# microzed_schematic.net
KiCad netlist of a schematic drawn in Altium Designer
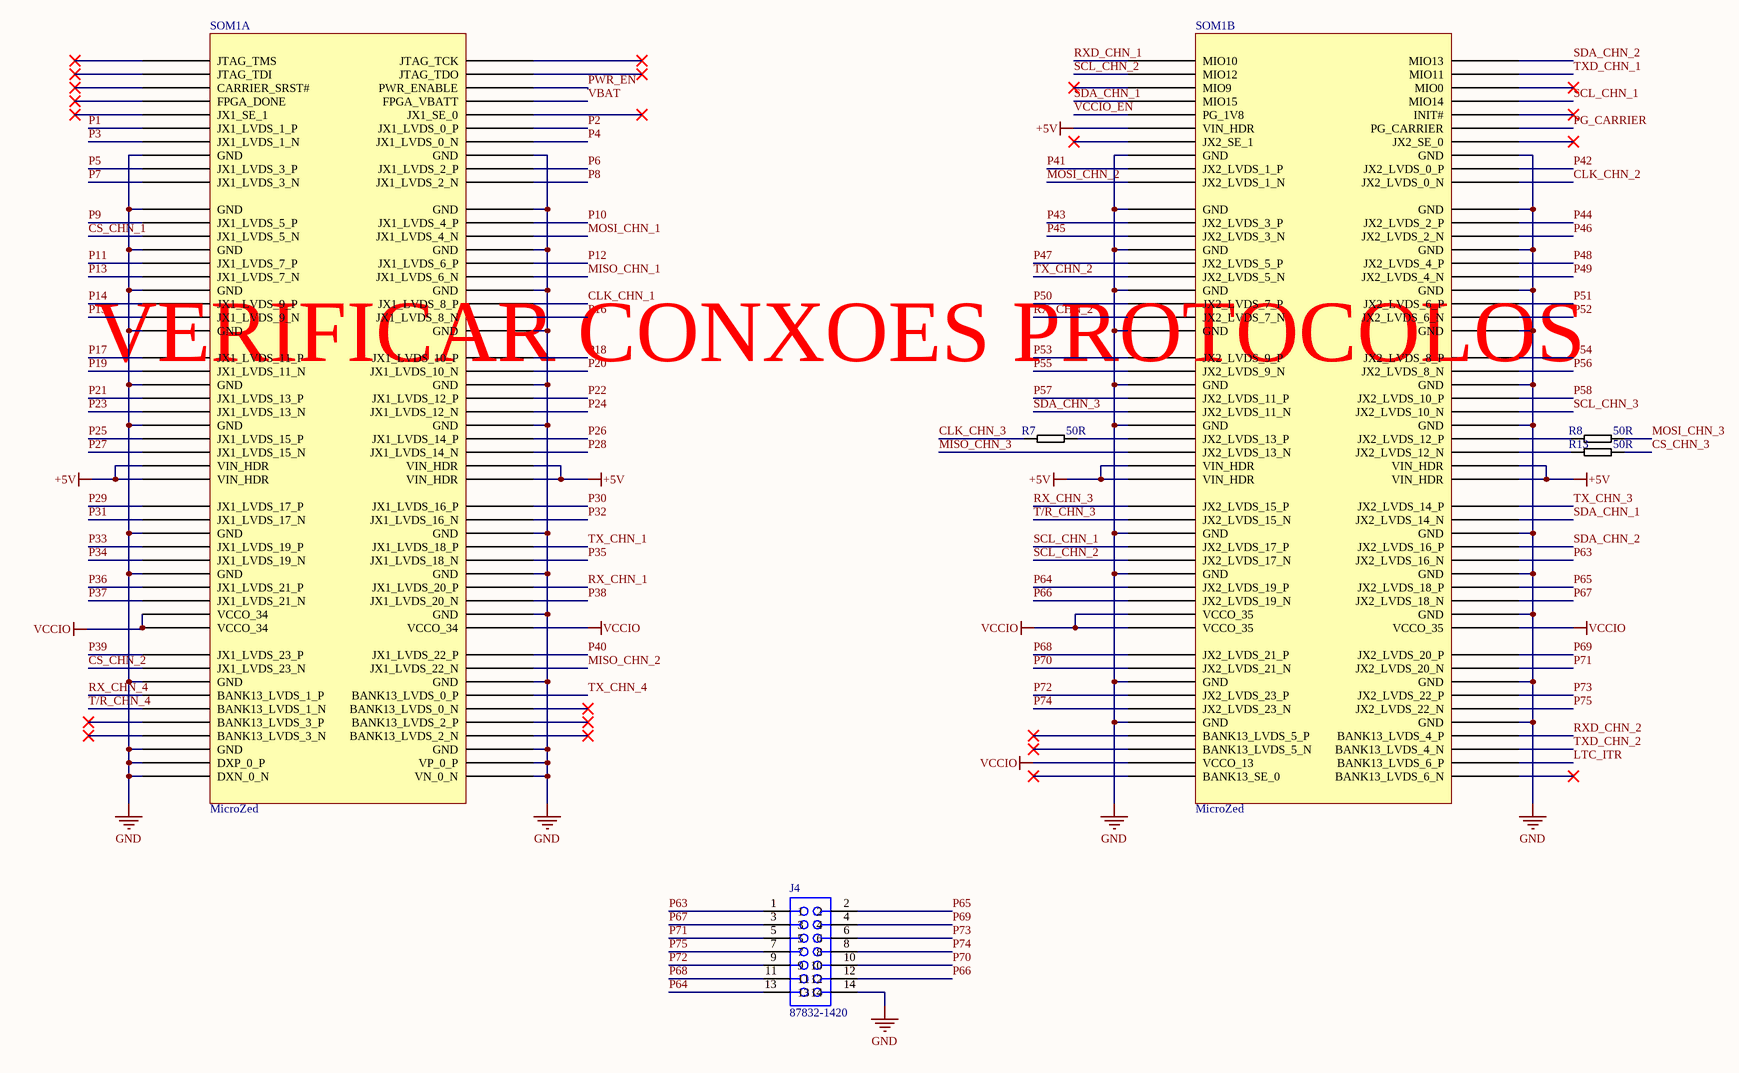
[diagram p0: microzed_schematic.SchDoc]

(export (version "E")
  (design (tool "Eeschema 10.0.6"))
  (components
    (comp (ref "J4")
      (value "87832-1420")
      (footprint "SAMTEC_TSW-107-05-F-D")
      (description "Connector Header Surface Mount 14 position 0.079 _2.00mm_")
      (fields (field (name "MF") "Molex") (field (name "MANUFACTURER PART NUMBER") "TSW-107-05-F-D"))
      (libsource (lib "flatsat_platform_2") (part "87832-1420"))
    )
    (comp (ref "R7")
      (value "50R")
      (footprint "R0603_HD")
      (description "RES SMD 50 OHM 1% 1/10W 0603")
      (fields (field (name "MANUFACTURER") "Vishay Dale") (field (name "TOLERANCE") "1%"))
      (libsource (lib "Resistor") (part "CRCW060350R0FKEA"))
    )
    (comp (ref "R8")
      (value "50R")
      (footprint "R0603_HD")
      (description "RES SMD 50 OHM 1% 1/10W 0603")
      (fields (field (name "MANUFACTURER") "Vishay Dale") (field (name "TOLERANCE") "1%"))
      (libsource (lib "Resistor") (part "CRCW060350R0FKEA"))
    )
    (comp (ref "R13")
      (value "50R")
      (footprint "R0603_HD")
      (description "RES SMD 50 OHM 1% 1/10W 0603")
      (fields (field (name "MANUFACTURER") "Vishay Dale") (field (name "TOLERANCE") "1%"))
      (libsource (lib "Resistor") (part "CRCW060350R0FKEA"))
    )
    (comp (ref "SOM1")
      (value "MicroZed")
      (footprint "MicroZedSOM")
      (description "MicroZed SOM Carrier Footprint")
      (fields (field (name "MANUFACTURER PART NUMBER") "61083-101400LF"))
      (libsource (lib "flatsat_platform_2") (part "MicroZed_SOM"))
    )
  )
  (nets
    (net (code "1") (name "+5V") (class "Default")
      (node (ref "SOM1") (pin "JX1-57") (pinfunction "VIN_HDR_JX1-57") (pintype "passive"))
      (node (ref "SOM1") (pin "JX1-58") (pinfunction "VIN_HDR_JX1-58") (pintype "passive"))
      (node (ref "SOM1") (pin "JX1-59") (pinfunction "VIN_HDR_JX1-59") (pintype "passive"))
      (node (ref "SOM1") (pin "JX1-60") (pinfunction "VIN_HDR_JX1-60") (pintype "passive"))
      (node (ref "SOM1") (pin "JX2-12") (pinfunction "VIN_HDR_JX2-12") (pintype "passive"))
      (node (ref "SOM1") (pin "JX2-57") (pinfunction "VIN_HDR_JX2-57") (pintype "passive"))
      (node (ref "SOM1") (pin "JX2-58") (pinfunction "VIN_HDR_JX2-58") (pintype "passive"))
      (node (ref "SOM1") (pin "JX2-59") (pinfunction "VIN_HDR_JX2-59") (pintype "passive"))
      (node (ref "SOM1") (pin "JX2-60") (pinfunction "VIN_HDR_JX2-60") (pintype "passive"))
    )
    (net (code "2") (name "/CLK_CHN_1") (class "Default")
      (node (ref "SOM1") (pin "JX1-35") (pinfunction "JX1_LVDS_8_P_JX1-35") (pintype "passive"))
    )
    (net (code "3") (name "/CLK_CHN_2") (class "Default")
      (node (ref "SOM1") (pin "JX2-19") (pinfunction "JX2_LVDS_0_N_JX2-19") (pintype "passive"))
    )
    (net (code "4") (name "/CLK_CHN_3") (class "Default")
      (node (ref "R7") (pin "1") (pinfunction "1_1") (pintype "passive"))
    )
    (net (code "5") (name "/CS_CHN_1") (class "Default")
      (node (ref "SOM1") (pin "JX1-26") (pinfunction "JX1_LVDS_5_N_JX1-26") (pintype "passive"))
    )
    (net (code "6") (name "/CS_CHN_2") (class "Default")
      (node (ref "SOM1") (pin "JX1-84") (pinfunction "JX1_LVDS_23_N_JX1-84") (pintype "passive"))
    )
    (net (code "7") (name "/CS_CHN_3") (class "Default")
      (node (ref "R13") (pin "2") (pinfunction "2_2") (pintype "passive"))
    )
    (net (code "8") (name "/LTC_ITR") (class "Default")
      (node (ref "SOM1") (pin "JX2-97") (pinfunction "BANK13_LVDS_6_P_JX2-97") (pintype "passive"))
    )
    (net (code "9") (name "/MISO_CHN_1") (class "Default")
      (node (ref "SOM1") (pin "JX1-31") (pinfunction "JX1_LVDS_6_N_JX1-31") (pintype "passive"))
    )
    (net (code "10") (name "/MISO_CHN_2") (class "Default")
      (node (ref "SOM1") (pin "JX1-83") (pinfunction "JX1_LVDS_22_N_JX1-83") (pintype "passive"))
    )
    (net (code "11") (name "/MISO_CHN_3") (class "Default")
      (node (ref "SOM1") (pin "JX2-56") (pinfunction "JX2_LVDS_13_N_JX2-56") (pintype "passive"))
    )
    (net (code "12") (name "/MOSI_CHN_1") (class "Default")
      (node (ref "SOM1") (pin "JX1-25") (pinfunction "JX1_LVDS_4_N_JX1-25") (pintype "passive"))
    )
    (net (code "13") (name "/MOSI_CHN_2") (class "Default")
      (node (ref "SOM1") (pin "JX2-20") (pinfunction "JX2_LVDS_1_N_JX2-20") (pintype "passive"))
    )
    (net (code "14") (name "/MOSI_CHN_3") (class "Default")
      (node (ref "R8") (pin "2") (pinfunction "2_2") (pintype "passive"))
    )
    (net (code "15") (name "/P1") (class "Default")
      (node (ref "SOM1") (pin "JX1-12") (pinfunction "JX1_LVDS_1_P_JX1-12") (pintype "passive"))
    )
    (net (code "16") (name "/P2") (class "Default")
      (node (ref "SOM1") (pin "JX1-11") (pinfunction "JX1_LVDS_0_P_JX1-11") (pintype "passive"))
    )
    (net (code "17") (name "/P3") (class "Default")
      (node (ref "SOM1") (pin "JX1-14") (pinfunction "JX1_LVDS_1_N_JX1-14") (pintype "passive"))
    )
    (net (code "18") (name "/P4") (class "Default")
      (node (ref "SOM1") (pin "JX1-13") (pinfunction "JX1_LVDS_0_N_JX1-13") (pintype "passive"))
    )
    (net (code "19") (name "/P5") (class "Default")
      (node (ref "SOM1") (pin "JX1-18") (pinfunction "JX1_LVDS_3_P_JX1-18") (pintype "passive"))
    )
    (net (code "20") (name "/P6") (class "Default")
      (node (ref "SOM1") (pin "JX1-17") (pinfunction "JX1_LVDS_2_P_JX1-17") (pintype "passive"))
    )
    (net (code "21") (name "/P7") (class "Default")
      (node (ref "SOM1") (pin "JX1-20") (pinfunction "JX1_LVDS_3_N_JX1-20") (pintype "passive"))
    )
    (net (code "22") (name "/P8") (class "Default")
      (node (ref "SOM1") (pin "JX1-19") (pinfunction "JX1_LVDS_2_N_JX1-19") (pintype "passive"))
    )
    (net (code "23") (name "/P9") (class "Default")
      (node (ref "SOM1") (pin "JX1-24") (pinfunction "JX1_LVDS_5_P_JX1-24") (pintype "passive"))
    )
    (net (code "24") (name "/P10") (class "Default")
      (node (ref "SOM1") (pin "JX1-23") (pinfunction "JX1_LVDS_4_P_JX1-23") (pintype "passive"))
    )
    (net (code "25") (name "/P11") (class "Default")
      (node (ref "SOM1") (pin "JX1-30") (pinfunction "JX1_LVDS_7_P_JX1-30") (pintype "passive"))
    )
    (net (code "26") (name "/P12") (class "Default")
      (node (ref "SOM1") (pin "JX1-29") (pinfunction "JX1_LVDS_6_P_JX1-29") (pintype "passive"))
    )
    (net (code "27") (name "/P13") (class "Default")
      (node (ref "SOM1") (pin "JX1-32") (pinfunction "JX1_LVDS_7_N_JX1-32") (pintype "passive"))
    )
    (net (code "28") (name "/P14") (class "Default")
      (node (ref "SOM1") (pin "JX1-36") (pinfunction "JX1_LVDS_9_P_JX1-36") (pintype "passive"))
    )
    (net (code "29") (name "/P15") (class "Default")
      (node (ref "SOM1") (pin "JX1-38") (pinfunction "JX1_LVDS_9_N_JX1-38") (pintype "passive"))
    )
    (net (code "30") (name "/P16") (class "Default")
      (node (ref "SOM1") (pin "JX1-37") (pinfunction "JX1_LVDS_8_N_JX1-37") (pintype "passive"))
    )
    (net (code "31") (name "/P17") (class "Default")
      (node (ref "SOM1") (pin "JX1-42") (pinfunction "JX1_LVDS_11_P_JX1-42") (pintype "passive"))
    )
    (net (code "32") (name "/P18") (class "Default")
      (node (ref "SOM1") (pin "JX1-41") (pinfunction "JX1_LVDS_10_P_JX1-41") (pintype "passive"))
    )
    (net (code "33") (name "/P19") (class "Default")
      (node (ref "SOM1") (pin "JX1-44") (pinfunction "JX1_LVDS_11_N_JX1-44") (pintype "passive"))
    )
    (net (code "34") (name "/P20") (class "Default")
      (node (ref "SOM1") (pin "JX1-43") (pinfunction "JX1_LVDS_10_N_JX1-43") (pintype "passive"))
    )
    (net (code "35") (name "/P21") (class "Default")
      (node (ref "SOM1") (pin "JX1-48") (pinfunction "JX1_LVDS_13_P_JX1-48") (pintype "passive"))
    )
    (net (code "36") (name "/P22") (class "Default")
      (node (ref "SOM1") (pin "JX1-47") (pinfunction "JX1_LVDS_12_P_JX1-47") (pintype "passive"))
    )
    (net (code "37") (name "/P23") (class "Default")
      (node (ref "SOM1") (pin "JX1-50") (pinfunction "JX1_LVDS_13_N_JX1-50") (pintype "passive"))
    )
    (net (code "38") (name "/P24") (class "Default")
      (node (ref "SOM1") (pin "JX1-49") (pinfunction "JX1_LVDS_12_N_JX1-49") (pintype "passive"))
    )
    (net (code "39") (name "/P25") (class "Default")
      (node (ref "SOM1") (pin "JX1-54") (pinfunction "JX1_LVDS_15_P_JX1-54") (pintype "passive"))
    )
    (net (code "40") (name "/P26") (class "Default")
      (node (ref "SOM1") (pin "JX1-53") (pinfunction "JX1_LVDS_14_P_JX1-53") (pintype "passive"))
    )
    (net (code "41") (name "/P27") (class "Default")
      (node (ref "SOM1") (pin "JX1-56") (pinfunction "JX1_LVDS_15_N_JX1-56") (pintype "passive"))
    )
    (net (code "42") (name "/P28") (class "Default")
      (node (ref "SOM1") (pin "JX1-55") (pinfunction "JX1_LVDS_14_N_JX1-55") (pintype "passive"))
    )
    (net (code "43") (name "/P29") (class "Default")
      (node (ref "SOM1") (pin "JX1-62") (pinfunction "JX1_LVDS_17_P_JX1-62") (pintype "passive"))
    )
    (net (code "44") (name "/P30") (class "Default")
      (node (ref "SOM1") (pin "JX1-61") (pinfunction "JX1_LVDS_16_P_JX1-61") (pintype "passive"))
    )
    (net (code "45") (name "/P31") (class "Default")
      (node (ref "SOM1") (pin "JX1-64") (pinfunction "JX1_LVDS_17_N_JX1-64") (pintype "passive"))
    )
    (net (code "46") (name "/P32") (class "Default")
      (node (ref "SOM1") (pin "JX1-63") (pinfunction "JX1_LVDS_16_N_JX1-63") (pintype "passive"))
    )
    (net (code "47") (name "/P33") (class "Default")
      (node (ref "SOM1") (pin "JX1-68") (pinfunction "JX1_LVDS_19_P_JX1-68") (pintype "passive"))
    )
    (net (code "48") (name "/P34") (class "Default")
      (node (ref "SOM1") (pin "JX1-70") (pinfunction "JX1_LVDS_19_N_JX1-70") (pintype "passive"))
    )
    (net (code "49") (name "/P35") (class "Default")
      (node (ref "SOM1") (pin "JX1-69") (pinfunction "JX1_LVDS_18_N_JX1-69") (pintype "passive"))
    )
    (net (code "50") (name "/P36") (class "Default")
      (node (ref "SOM1") (pin "JX1-74") (pinfunction "JX1_LVDS_21_P_JX1-74") (pintype "passive"))
    )
    (net (code "51") (name "/P37") (class "Default")
      (node (ref "SOM1") (pin "JX1-76") (pinfunction "JX1_LVDS_21_N_JX1-76") (pintype "passive"))
    )
    (net (code "52") (name "/P38") (class "Default")
      (node (ref "SOM1") (pin "JX1-75") (pinfunction "JX1_LVDS_20_N_JX1-75") (pintype "passive"))
    )
    (net (code "53") (name "/P39") (class "Default")
      (node (ref "SOM1") (pin "JX1-82") (pinfunction "JX1_LVDS_23_P_JX1-82") (pintype "passive"))
    )
    (net (code "54") (name "/P40") (class "Default")
      (node (ref "SOM1") (pin "JX1-81") (pinfunction "JX1_LVDS_22_P_JX1-81") (pintype "passive"))
    )
    (net (code "55") (name "/P41") (class "Default")
      (node (ref "SOM1") (pin "JX2-18") (pinfunction "JX2_LVDS_1_P_JX2-18") (pintype "passive"))
    )
    (net (code "56") (name "/P42") (class "Default")
      (node (ref "SOM1") (pin "JX2-17") (pinfunction "JX2_LVDS_0_P_JX2-17") (pintype "passive"))
    )
    (net (code "57") (name "/P43") (class "Default")
      (node (ref "SOM1") (pin "JX2-24") (pinfunction "JX2_LVDS_3_P_JX2-24") (pintype "passive"))
    )
    (net (code "58") (name "/P44") (class "Default")
      (node (ref "SOM1") (pin "JX2-23") (pinfunction "JX2_LVDS_2_P_JX2-23") (pintype "passive"))
    )
    (net (code "59") (name "/P45") (class "Default")
      (node (ref "SOM1") (pin "JX2-26") (pinfunction "JX2_LVDS_3_N_JX2-26") (pintype "passive"))
    )
    (net (code "60") (name "/P46") (class "Default")
      (node (ref "SOM1") (pin "JX2-25") (pinfunction "JX2_LVDS_2_N_JX2-25") (pintype "passive"))
    )
    (net (code "61") (name "/P47") (class "Default")
      (node (ref "SOM1") (pin "JX2-30") (pinfunction "JX2_LVDS_5_P_JX2-30") (pintype "passive"))
    )
    (net (code "62") (name "/P48") (class "Default")
      (node (ref "SOM1") (pin "JX2-29") (pinfunction "JX2_LVDS_4_P_JX2-29") (pintype "passive"))
    )
    (net (code "63") (name "/P49") (class "Default")
      (node (ref "SOM1") (pin "JX2-31") (pinfunction "JX2_LVDS_4_N_JX2-31") (pintype "passive"))
    )
    (net (code "64") (name "/P50") (class "Default")
      (node (ref "SOM1") (pin "JX2-36") (pinfunction "JX2_LVDS_7_P_JX2-36") (pintype "passive"))
    )
    (net (code "65") (name "/P51") (class "Default")
      (node (ref "SOM1") (pin "JX2-35") (pinfunction "JX2_LVDS_6_P_JX2-35") (pintype "passive"))
    )
    (net (code "66") (name "/P52") (class "Default")
      (node (ref "SOM1") (pin "JX2-37") (pinfunction "JX2_LVDS_6_N_JX2-37") (pintype "passive"))
    )
    (net (code "67") (name "/P53") (class "Default")
      (node (ref "SOM1") (pin "JX2-42") (pinfunction "JX2_LVDS_9_P_JX2-42") (pintype "passive"))
    )
    (net (code "68") (name "/P54") (class "Default")
      (node (ref "SOM1") (pin "JX2-41") (pinfunction "JX2_LVDS_8_P_JX2-41") (pintype "passive"))
    )
    (net (code "69") (name "/P55") (class "Default")
      (node (ref "SOM1") (pin "JX2-44") (pinfunction "JX2_LVDS_9_N_JX2-44") (pintype "passive"))
    )
    (net (code "70") (name "/P56") (class "Default")
      (node (ref "SOM1") (pin "JX2-43") (pinfunction "JX2_LVDS_8_N_JX2-43") (pintype "passive"))
    )
    (net (code "71") (name "/P57") (class "Default")
      (node (ref "SOM1") (pin "JX2-48") (pinfunction "JX2_LVDS_11_P_JX2-48") (pintype "passive"))
    )
    (net (code "72") (name "/P58") (class "Default")
      (node (ref "SOM1") (pin "JX2-47") (pinfunction "JX2_LVDS_10_P_JX2-47") (pintype "passive"))
    )
    (net (code "73") (name "/P63") (class "Default")
      (node (ref "J4") (pin "1") (pinfunction "1_1") (pintype "passive"))
      (node (ref "SOM1") (pin "JX2-69") (pinfunction "JX2_LVDS_16_N_JX2-69") (pintype "passive"))
    )
    (net (code "74") (name "/P64") (class "Default")
      (node (ref "J4") (pin "13") (pinfunction "13_13") (pintype "passive"))
      (node (ref "SOM1") (pin "JX2-74") (pinfunction "JX2_LVDS_19_P_JX2-74") (pintype "passive"))
    )
    (net (code "75") (name "/P65") (class "Default")
      (node (ref "J4") (pin "2") (pinfunction "2_2") (pintype "passive"))
      (node (ref "SOM1") (pin "JX2-73") (pinfunction "JX2_LVDS_18_P_JX2-73") (pintype "passive"))
    )
    (net (code "76") (name "/P66") (class "Default")
      (node (ref "J4") (pin "12") (pinfunction "12_12") (pintype "passive"))
      (node (ref "SOM1") (pin "JX2-76") (pinfunction "JX2_LVDS_19_N_JX2-76") (pintype "passive"))
    )
    (net (code "77") (name "/P67") (class "Default")
      (node (ref "J4") (pin "3") (pinfunction "3_3") (pintype "passive"))
      (node (ref "SOM1") (pin "JX2-75") (pinfunction "JX2_LVDS_18_N_JX2-75") (pintype "passive"))
    )
    (net (code "78") (name "/P68") (class "Default")
      (node (ref "J4") (pin "11") (pinfunction "11_11") (pintype "passive"))
      (node (ref "SOM1") (pin "JX2-82") (pinfunction "JX2_LVDS_21_P_JX2-82") (pintype "passive"))
    )
    (net (code "79") (name "/P69") (class "Default")
      (node (ref "J4") (pin "4") (pinfunction "4_4") (pintype "passive"))
      (node (ref "SOM1") (pin "JX2-81") (pinfunction "JX2_LVDS_20_P_JX2-81") (pintype "passive"))
    )
    (net (code "80") (name "/P70") (class "Default")
      (node (ref "J4") (pin "10") (pinfunction "10_10") (pintype "passive"))
      (node (ref "SOM1") (pin "JX2-84") (pinfunction "JX2_LVDS_21_N_JX2-84") (pintype "passive"))
    )
    (net (code "81") (name "/P71") (class "Default")
      (node (ref "J4") (pin "5") (pinfunction "5_5") (pintype "passive"))
      (node (ref "SOM1") (pin "JX2-83") (pinfunction "JX2_LVDS_20_N_JX2-83") (pintype "passive"))
    )
    (net (code "82") (name "/P72") (class "Default")
      (node (ref "J4") (pin "9") (pinfunction "9_9") (pintype "passive"))
      (node (ref "SOM1") (pin "JX2-88") (pinfunction "JX2_LVDS_23_P_JX2-88") (pintype "passive"))
    )
    (net (code "83") (name "/P73") (class "Default")
      (node (ref "J4") (pin "6") (pinfunction "6_6") (pintype "passive"))
      (node (ref "SOM1") (pin "JX2-87") (pinfunction "JX2_LVDS_22_P_JX2-87") (pintype "passive"))
    )
    (net (code "84") (name "/P74") (class "Default")
      (node (ref "J4") (pin "8") (pinfunction "8_8") (pintype "passive"))
      (node (ref "SOM1") (pin "JX2-90") (pinfunction "JX2_LVDS_23_N_JX2-90") (pintype "passive"))
    )
    (net (code "85") (name "/P75") (class "Default")
      (node (ref "J4") (pin "7") (pinfunction "7_7") (pintype "passive"))
      (node (ref "SOM1") (pin "JX2-89") (pinfunction "JX2_LVDS_22_N_JX2-89") (pintype "passive"))
    )
    (net (code "86") (name "/PG_CARRIER") (class "Default")
      (node (ref "SOM1") (pin "JX2-11") (pinfunction "PG_CARRIER_JX2-11") (pintype "passive"))
    )
    (net (code "87") (name "/PWR_EN") (class "Default")
      (node (ref "SOM1") (pin "JX1-5") (pinfunction "PWR_ENABLE_JX1-5") (pintype "passive"))
    )
    (net (code "88") (name "/RXD_CHN_1") (class "Default")
      (node (ref "SOM1") (pin "JX2-2") (pinfunction "MIO10_JX2-2") (pintype "passive"))
    )
    (net (code "89") (name "/RXD_CHN_2") (class "Default")
      (node (ref "SOM1") (pin "JX2-93") (pinfunction "BANK13_LVDS_4_P_JX2-93") (pintype "passive"))
    )
    (net (code "90") (name "/RX_CHN_1") (class "Default")
      (node (ref "SOM1") (pin "JX1-73") (pinfunction "JX1_LVDS_20_P_JX1-73") (pintype "passive"))
    )
    (net (code "91") (name "/RX_CHN_2") (class "Default")
      (node (ref "SOM1") (pin "JX2-38") (pinfunction "JX2_LVDS_7_N_JX2-38") (pintype "passive"))
    )
    (net (code "92") (name "/RX_CHN_3") (class "Default")
      (node (ref "SOM1") (pin "JX2-62") (pinfunction "JX2_LVDS_15_P_JX2-62") (pintype "passive"))
    )
    (net (code "93") (name "/RX_CHN_4") (class "Default")
      (node (ref "SOM1") (pin "JX1-88") (pinfunction "BANK13_LVDS_1_P_JX1-88") (pintype "passive"))
    )
    (net (code "94") (name "/SCL_CHN_1") (class "Default")
      (node (ref "SOM1") (pin "JX2-68") (pinfunction "JX2_LVDS_17_P_JX2-68") (pintype "passive"))
      (node (ref "SOM1") (pin "JX2-7") (pinfunction "MIO14_JX2-7") (pintype "passive"))
    )
    (net (code "95") (name "/SCL_CHN_2") (class "Default")
      (node (ref "SOM1") (pin "JX2-4") (pinfunction "MIO12_JX2-4") (pintype "passive"))
      (node (ref "SOM1") (pin "JX2-70") (pinfunction "JX2_LVDS_17_N_JX2-70") (pintype "passive"))
    )
    (net (code "96") (name "/SCL_CHN_3") (class "Default")
      (node (ref "SOM1") (pin "JX2-49") (pinfunction "JX2_LVDS_10_N_JX2-49") (pintype "passive"))
    )
    (net (code "97") (name "/SDA_CHN_1") (class "Default")
      (node (ref "SOM1") (pin "JX2-63") (pinfunction "JX2_LVDS_14_N_JX2-63") (pintype "passive"))
      (node (ref "SOM1") (pin "JX2-8") (pinfunction "MIO15_JX2-8") (pintype "passive"))
    )
    (net (code "98") (name "/SDA_CHN_2") (class "Default")
      (node (ref "SOM1") (pin "JX2-1") (pinfunction "MIO13_JX2-1") (pintype "passive"))
      (node (ref "SOM1") (pin "JX2-67") (pinfunction "JX2_LVDS_16_P_JX2-67") (pintype "passive"))
    )
    (net (code "99") (name "/SDA_CHN_3") (class "Default")
      (node (ref "SOM1") (pin "JX2-50") (pinfunction "JX2_LVDS_11_N_JX2-50") (pintype "passive"))
    )
    (net (code "100") (name "/TXD_CHN_1") (class "Default")
      (node (ref "SOM1") (pin "JX2-3") (pinfunction "MIO11_JX2-3") (pintype "passive"))
    )
    (net (code "101") (name "/TXD_CHN_2") (class "Default")
      (node (ref "SOM1") (pin "JX2-95") (pinfunction "BANK13_LVDS_4_N_JX2-95") (pintype "passive"))
    )
    (net (code "102") (name "/TX_CHN_1") (class "Default")
      (node (ref "SOM1") (pin "JX1-67") (pinfunction "JX1_LVDS_18_P_JX1-67") (pintype "passive"))
    )
    (net (code "103") (name "/TX_CHN_2") (class "Default")
      (node (ref "SOM1") (pin "JX2-32") (pinfunction "JX2_LVDS_5_N_JX2-32") (pintype "passive"))
    )
    (net (code "104") (name "/TX_CHN_3") (class "Default")
      (node (ref "SOM1") (pin "JX2-61") (pinfunction "JX2_LVDS_14_P_JX2-61") (pintype "passive"))
    )
    (net (code "105") (name "/TX_CHN_4") (class "Default")
      (node (ref "SOM1") (pin "JX1-87") (pinfunction "BANK13_LVDS_0_P_JX1-87") (pintype "passive"))
    )
    (net (code "106") (name "/T{slash}R_CHN_3") (class "Default")
      (node (ref "SOM1") (pin "JX2-64") (pinfunction "JX2_LVDS_15_N_JX2-64") (pintype "passive"))
    )
    (net (code "107") (name "/T{slash}R_CHN_4") (class "Default")
      (node (ref "SOM1") (pin "JX1-90") (pinfunction "BANK13_LVDS_1_N_JX1-90") (pintype "passive"))
    )
    (net (code "108") (name "/VBAT") (class "Default")
      (node (ref "SOM1") (pin "JX1-7") (pinfunction "FPGA_VBATT_JX1-7") (pintype "passive"))
    )
    (net (code "109") (name "/VCCIO_EN") (class "Default")
      (node (ref "SOM1") (pin "JX2-10") (pinfunction "PG_1V8_JX2-10") (pintype "passive"))
    )
    (net (code "110") (name "GND") (class "Default")
      (node (ref "J4") (pin "14") (pinfunction "14_14") (pintype "passive"))
      (node (ref "SOM1") (pin "JX1-100") (pinfunction "DXN_0_N_JX1-100") (pintype "passive"))
      (node (ref "SOM1") (pin "JX1-15") (pinfunction "GND_JX1-15") (pintype "passive"))
      (node (ref "SOM1") (pin "JX1-16") (pinfunction "GND_JX1-16") (pintype "passive"))
      (node (ref "SOM1") (pin "JX1-21") (pinfunction "GND_JX1-21") (pintype "passive"))
      (node (ref "SOM1") (pin "JX1-22") (pinfunction "GND_JX1-22") (pintype "passive"))
      (node (ref "SOM1") (pin "JX1-27") (pinfunction "GND_JX1-27") (pintype "passive"))
      (node (ref "SOM1") (pin "JX1-28") (pinfunction "GND_JX1-28") (pintype "passive"))
      (node (ref "SOM1") (pin "JX1-33") (pinfunction "GND_JX1-33") (pintype "passive"))
      (node (ref "SOM1") (pin "JX1-34") (pinfunction "GND_JX1-34") (pintype "passive"))
      (node (ref "SOM1") (pin "JX1-39") (pinfunction "GND_JX1-39") (pintype "passive"))
      (node (ref "SOM1") (pin "JX1-40") (pinfunction "GND_JX1-40") (pintype "passive"))
      (node (ref "SOM1") (pin "JX1-45") (pinfunction "GND_JX1-45") (pintype "passive"))
      (node (ref "SOM1") (pin "JX1-46") (pinfunction "GND_JX1-46") (pintype "passive"))
      (node (ref "SOM1") (pin "JX1-51") (pinfunction "GND_JX1-51") (pintype "passive"))
      (node (ref "SOM1") (pin "JX1-52") (pinfunction "GND_JX1-52") (pintype "passive"))
      (node (ref "SOM1") (pin "JX1-65") (pinfunction "GND_JX1-65") (pintype "passive"))
      (node (ref "SOM1") (pin "JX1-66") (pinfunction "GND_JX1-66") (pintype "passive"))
      (node (ref "SOM1") (pin "JX1-71") (pinfunction "GND_JX1-71") (pintype "passive"))
      (node (ref "SOM1") (pin "JX1-72") (pinfunction "GND_JX1-72") (pintype "passive"))
      (node (ref "SOM1") (pin "JX1-77") (pinfunction "GND_JX1-77") (pintype "passive"))
      (node (ref "SOM1") (pin "JX1-85") (pinfunction "GND_JX1-85") (pintype "passive"))
      (node (ref "SOM1") (pin "JX1-86") (pinfunction "GND_JX1-86") (pintype "passive"))
      (node (ref "SOM1") (pin "JX1-95") (pinfunction "GND_JX1-95") (pintype "passive"))
      (node (ref "SOM1") (pin "JX1-96") (pinfunction "GND_JX1-96") (pintype "passive"))
      (node (ref "SOM1") (pin "JX1-97") (pinfunction "VP_0_P_JX1-97") (pintype "passive"))
      (node (ref "SOM1") (pin "JX1-98") (pinfunction "DXP_0_P_JX1-98") (pintype "passive"))
      (node (ref "SOM1") (pin "JX1-99") (pinfunction "VN_0_N_JX1-99") (pintype "passive"))
      (node (ref "SOM1") (pin "JX2-15") (pinfunction "GND_JX2-15") (pintype "passive"))
      (node (ref "SOM1") (pin "JX2-16") (pinfunction "GND_JX2-16") (pintype "passive"))
      (node (ref "SOM1") (pin "JX2-21") (pinfunction "GND_JX2-21") (pintype "passive"))
      (node (ref "SOM1") (pin "JX2-22") (pinfunction "GND_JX2-22") (pintype "passive"))
      (node (ref "SOM1") (pin "JX2-27") (pinfunction "GND_JX2-27") (pintype "passive"))
      (node (ref "SOM1") (pin "JX2-28") (pinfunction "GND_JX2-28") (pintype "passive"))
      (node (ref "SOM1") (pin "JX2-33") (pinfunction "GND_JX2-33") (pintype "passive"))
      (node (ref "SOM1") (pin "JX2-34") (pinfunction "GND_JX2-34") (pintype "passive"))
      (node (ref "SOM1") (pin "JX2-39") (pinfunction "GND_JX2-39") (pintype "passive"))
      (node (ref "SOM1") (pin "JX2-40") (pinfunction "GND_JX2-40") (pintype "passive"))
      (node (ref "SOM1") (pin "JX2-45") (pinfunction "GND_JX2-45") (pintype "passive"))
      (node (ref "SOM1") (pin "JX2-46") (pinfunction "GND_JX2-46") (pintype "passive"))
      (node (ref "SOM1") (pin "JX2-51") (pinfunction "GND_JX2-51") (pintype "passive"))
      (node (ref "SOM1") (pin "JX2-52") (pinfunction "GND_JX2-52") (pintype "passive"))
      (node (ref "SOM1") (pin "JX2-65") (pinfunction "GND_JX2-65") (pintype "passive"))
      (node (ref "SOM1") (pin "JX2-66") (pinfunction "GND_JX2-66") (pintype "passive"))
      (node (ref "SOM1") (pin "JX2-71") (pinfunction "GND_JX2-71") (pintype "passive"))
      (node (ref "SOM1") (pin "JX2-72") (pinfunction "GND_JX2-72") (pintype "passive"))
      (node (ref "SOM1") (pin "JX2-77") (pinfunction "GND_JX2-77") (pintype "passive"))
      (node (ref "SOM1") (pin "JX2-85") (pinfunction "GND_JX2-85") (pintype "passive"))
      (node (ref "SOM1") (pin "JX2-86") (pinfunction "GND_JX2-86") (pintype "passive"))
      (node (ref "SOM1") (pin "JX2-91") (pinfunction "GND_JX2-91") (pintype "passive"))
      (node (ref "SOM1") (pin "JX2-92") (pinfunction "GND_JX2-92") (pintype "passive"))
    )
    (net (code "111") (name "Net-(SOM1B-JX2_LVDS_12_N)") (class "Default")
      (node (ref "R13") (pin "1") (pinfunction "1_1") (pintype "passive"))
      (node (ref "SOM1") (pin "JX2-55") (pinfunction "JX2_LVDS_12_N_JX2-55") (pintype "passive"))
    )
    (net (code "112") (name "Net-(SOM1B-JX2_LVDS_12_P)") (class "Default")
      (node (ref "R8") (pin "1") (pinfunction "1_1") (pintype "passive"))
      (node (ref "SOM1") (pin "JX2-53") (pinfunction "JX2_LVDS_12_P_JX2-53") (pintype "passive"))
    )
    (net (code "113") (name "Net-(SOM1B-JX2_LVDS_13_P)") (class "Default")
      (node (ref "R7") (pin "2") (pinfunction "2_2") (pintype "passive"))
      (node (ref "SOM1") (pin "JX2-54") (pinfunction "JX2_LVDS_13_P_JX2-54") (pintype "passive"))
    )
    (net (code "114") (name "VCCIO") (class "Default")
      (node (ref "SOM1") (pin "JX1-78") (pinfunction "VCCO_34_JX1-78") (pintype "passive"))
      (node (ref "SOM1") (pin "JX1-79") (pinfunction "VCCO_34_JX1-79") (pintype "passive"))
      (node (ref "SOM1") (pin "JX1-80") (pinfunction "VCCO_34_JX1-80") (pintype "passive"))
      (node (ref "SOM1") (pin "JX2-78") (pinfunction "VCCO_35_JX2-78") (pintype "passive"))
      (node (ref "SOM1") (pin "JX2-79") (pinfunction "VCCO_35_JX2-79") (pintype "passive"))
      (node (ref "SOM1") (pin "JX2-80") (pinfunction "VCCO_35_JX2-80") (pintype "passive"))
      (node (ref "SOM1") (pin "JX2-98") (pinfunction "VCCO_13_JX2-98") (pintype "passive"))
    )
    (net (code "115") (name "unconnected-(SOM1A-BANK13_LVDS_0_N-PadJX1-89)") (class "Default")
      (node (ref "SOM1") (pin "JX1-89") (pinfunction "BANK13_LVDS_0_N_JX1-89") (pintype "passive+no_connect"))
    )
    (net (code "116") (name "unconnected-(SOM1A-BANK13_LVDS_2_N-PadJX1-93)") (class "Default")
      (node (ref "SOM1") (pin "JX1-93") (pinfunction "BANK13_LVDS_2_N_JX1-93") (pintype "passive+no_connect"))
    )
    (net (code "117") (name "unconnected-(SOM1A-BANK13_LVDS_2_P-PadJX1-91)") (class "Default")
      (node (ref "SOM1") (pin "JX1-91") (pinfunction "BANK13_LVDS_2_P_JX1-91") (pintype "passive+no_connect"))
    )
    (net (code "118") (name "unconnected-(SOM1A-BANK13_LVDS_3_N-PadJX1-94)") (class "Default")
      (node (ref "SOM1") (pin "JX1-94") (pinfunction "BANK13_LVDS_3_N_JX1-94") (pintype "passive+no_connect"))
    )
    (net (code "119") (name "unconnected-(SOM1A-BANK13_LVDS_3_P-PadJX1-92)") (class "Default")
      (node (ref "SOM1") (pin "JX1-92") (pinfunction "BANK13_LVDS_3_P_JX1-92") (pintype "passive+no_connect"))
    )
    (net (code "120") (name "unconnected-(SOM1A-CARRIER_SRST#-PadJX1-6)") (class "Default")
      (node (ref "SOM1") (pin "JX1-6") (pinfunction "CARRIER_SRST#_JX1-6") (pintype "passive+no_connect"))
    )
    (net (code "121") (name "unconnected-(SOM1A-FPGA_DONE-PadJX1-8)") (class "Default")
      (node (ref "SOM1") (pin "JX1-8") (pinfunction "FPGA_DONE_JX1-8") (pintype "passive+no_connect"))
    )
    (net (code "122") (name "unconnected-(SOM1A-JTAG_TCK-PadJX1-1)") (class "Default")
      (node (ref "SOM1") (pin "JX1-1") (pinfunction "JTAG_TCK_JX1-1") (pintype "passive+no_connect"))
    )
    (net (code "123") (name "unconnected-(SOM1A-JTAG_TDI-PadJX1-4)") (class "Default")
      (node (ref "SOM1") (pin "JX1-4") (pinfunction "JTAG_TDI_JX1-4") (pintype "passive+no_connect"))
    )
    (net (code "124") (name "unconnected-(SOM1A-JTAG_TDO-PadJX1-3)") (class "Default")
      (node (ref "SOM1") (pin "JX1-3") (pinfunction "JTAG_TDO_JX1-3") (pintype "passive+no_connect"))
    )
    (net (code "125") (name "unconnected-(SOM1A-JTAG_TMS-PadJX1-2)") (class "Default")
      (node (ref "SOM1") (pin "JX1-2") (pinfunction "JTAG_TMS_JX1-2") (pintype "passive+no_connect"))
    )
    (net (code "126") (name "unconnected-(SOM1A-JX1_SE_0-PadJX1-9)") (class "Default")
      (node (ref "SOM1") (pin "JX1-9") (pinfunction "JX1_SE_0_JX1-9") (pintype "passive+no_connect"))
    )
    (net (code "127") (name "unconnected-(SOM1A-JX1_SE_1-PadJX1-10)") (class "Default")
      (node (ref "SOM1") (pin "JX1-10") (pinfunction "JX1_SE_1_JX1-10") (pintype "passive+no_connect"))
    )
    (net (code "128") (name "unconnected-(SOM1B-BANK13_LVDS_5_N-PadJX2-96)") (class "Default")
      (node (ref "SOM1") (pin "JX2-96") (pinfunction "BANK13_LVDS_5_N_JX2-96") (pintype "passive+no_connect"))
    )
    (net (code "129") (name "unconnected-(SOM1B-BANK13_LVDS_5_P-PadJX2-94)") (class "Default")
      (node (ref "SOM1") (pin "JX2-94") (pinfunction "BANK13_LVDS_5_P_JX2-94") (pintype "passive+no_connect"))
    )
    (net (code "130") (name "unconnected-(SOM1B-BANK13_LVDS_6_N-PadJX2-99)") (class "Default")
      (node (ref "SOM1") (pin "JX2-99") (pinfunction "BANK13_LVDS_6_N_JX2-99") (pintype "passive+no_connect"))
    )
    (net (code "131") (name "unconnected-(SOM1B-BANK13_SE_0-PadJX2-100)") (class "Default")
      (node (ref "SOM1") (pin "JX2-100") (pinfunction "BANK13_SE_0_JX2-100") (pintype "passive+no_connect"))
    )
    (net (code "132") (name "unconnected-(SOM1B-INIT#-PadJX2-9)") (class "Default")
      (node (ref "SOM1") (pin "JX2-9") (pinfunction "INIT#_JX2-9") (pintype "passive+no_connect"))
    )
    (net (code "133") (name "unconnected-(SOM1B-JX2_SE_0-PadJX2-13)") (class "Default")
      (node (ref "SOM1") (pin "JX2-13") (pinfunction "JX2_SE_0_JX2-13") (pintype "passive+no_connect"))
    )
    (net (code "134") (name "unconnected-(SOM1B-JX2_SE_1-PadJX2-14)") (class "Default")
      (node (ref "SOM1") (pin "JX2-14") (pinfunction "JX2_SE_1_JX2-14") (pintype "passive+no_connect"))
    )
    (net (code "135") (name "unconnected-(SOM1B-MIO0-PadJX2-5)") (class "Default")
      (node (ref "SOM1") (pin "JX2-5") (pinfunction "MIO0_JX2-5") (pintype "passive+no_connect"))
    )
    (net (code "136") (name "unconnected-(SOM1B-MIO9-PadJX2-6)") (class "Default")
      (node (ref "SOM1") (pin "JX2-6") (pinfunction "MIO9_JX2-6") (pintype "passive+no_connect"))
    )
  )
)
